# op_amp.net
KiCad netlist of a schematic drawn in Altium Designer
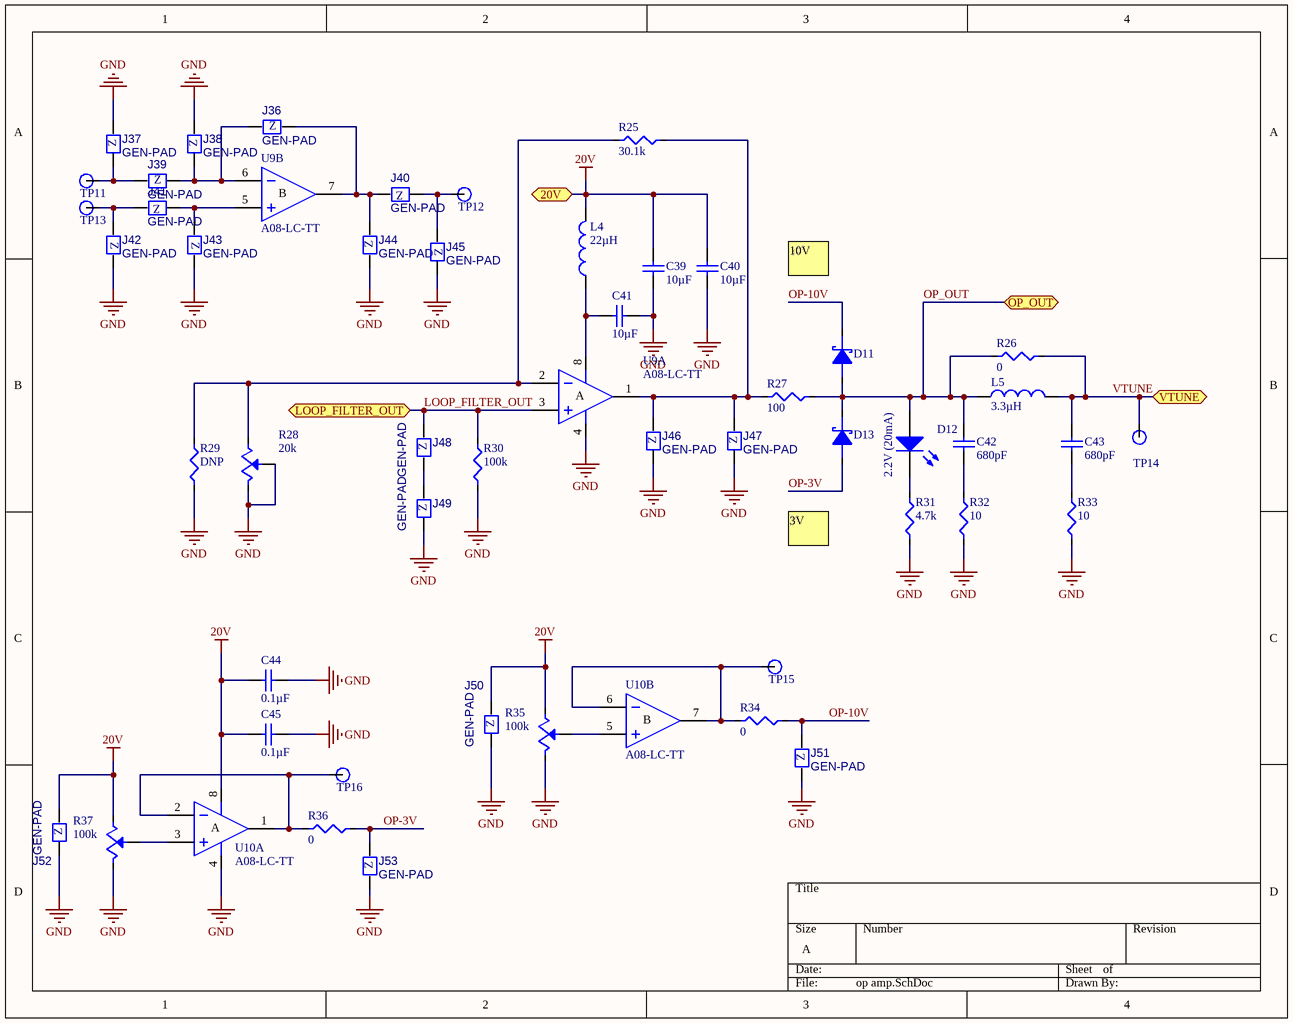
[diagram p0: op amp.SchDoc]

(export (version "E")
  (design (tool "Eeschema 10.0.6"))
  (components
    (comp (ref "C39")
      (value "10µF")
      (footprint "C1210-2.5mm")
      (description "Capacitor")
      (fields (field (name "EE PART NUMBER") "EE-CAP-00013") (field (name "VOLTAGE") "50V"))
      (libsource (lib "EE") (part "CAP"))
    )
    (comp (ref "C40")
      (value "10µF")
      (footprint "C1210-2.5mm")
      (description "Capacitor")
      (fields (field (name "EE PART NUMBER") "EE-CAP-00013") (field (name "VOLTAGE") "50V"))
      (libsource (lib "EE") (part "CAP"))
    )
    (comp (ref "C41")
      (value "10µF")
      (footprint "C1210-2.5mm")
      (description "Capacitor")
      (fields (field (name "EE PART NUMBER") "EE-CAP-00013") (field (name "VOLTAGE") "50V"))
      (libsource (lib "EE") (part "CAP"))
    )
    (comp (ref "C42")
      (value "680pF")
      (footprint "C0805-1.25MM")
      (description "Capacitor")
      (fields (field (name "EE PART NUMBER") "EE-CAP-00012") (field (name "VOLTAGE") "50V"))
      (libsource (lib "EE") (part "CAP"))
    )
    (comp (ref "C43")
      (value "680pF")
      (footprint "C0805-1.25MM")
      (description "Capacitor")
      (fields (field (name "EE PART NUMBER") "EE-CAP-00012") (field (name "VOLTAGE") "50V"))
      (libsource (lib "EE") (part "CAP"))
    )
    (comp (ref "C44")
      (value "0.1µF")
      (footprint "C0805-1.25MM")
      (description "Capacitor")
      (fields (field (name "EE PART NUMBER") "EE-CAP-00014") (field (name "VOLTAGE") "50V"))
      (libsource (lib "EE") (part "CAP"))
    )
    (comp (ref "C45")
      (value "0.1µF")
      (footprint "C0805-1.25MM")
      (description "Capacitor")
      (fields (field (name "EE PART NUMBER") "EE-CAP-00014") (field (name "VOLTAGE") "50V"))
      (libsource (lib "EE") (part "CAP"))
    )
    (comp (ref "D11")
      (value "SCHOTTKY")
      (footprint "SOD-123f")
      (description "Schottky Diode")
      (fields (field (name "EE PART NUMBER") "EE-DIODE-00002") (field (name "VOLTAGE") "30V"))
      (libsource (lib "EE") (part "SCHOTTKY"))
    )
    (comp (ref "D12")
      (value "2.2V (20mA)")
      (footprint "0805-LED")
      (description "LED")
      (fields (field (name "EE PART NUMBER") "EE-DIODE-00003") (field (name "VOLTAGE") "2.2V"))
      (libsource (lib "EE") (part "LED"))
    )
    (comp (ref "D13")
      (value "SCHOTTKY")
      (footprint "SOD-123f")
      (description "Schottky Diode")
      (fields (field (name "EE PART NUMBER") "EE-DIODE-00002") (field (name "VOLTAGE") "30V"))
      (libsource (lib "EE") (part "SCHOTTKY"))
    )
    (comp (ref "J36")
      (value "GEN-PAD")
      (footprint "0805-DNP")
      (description "Generic Component")
      (fields (field (name "EE PART NUMBER") "EE-GEN-00001"))
      (libsource (lib "EE") (part "GEN-PAD"))
    )
    (comp (ref "J37")
      (value "GEN-PAD")
      (footprint "0805-DNP")
      (description "Generic Component")
      (fields (field (name "EE PART NUMBER") "EE-GEN-00001"))
      (libsource (lib "EE") (part "GEN-PAD"))
    )
    (comp (ref "J38")
      (value "GEN-PAD")
      (footprint "0805-DNP")
      (description "Generic Component")
      (fields (field (name "EE PART NUMBER") "EE-GEN-00001"))
      (libsource (lib "EE") (part "GEN-PAD"))
    )
    (comp (ref "J39")
      (value "GEN-PAD")
      (footprint "0805-DNP")
      (description "Generic Component")
      (fields (field (name "EE PART NUMBER") "EE-GEN-00001"))
      (libsource (lib "EE") (part "GEN-PAD"))
    )
    (comp (ref "J40")
      (value "GEN-PAD")
      (footprint "0805-DNP")
      (description "Generic Component")
      (fields (field (name "EE PART NUMBER") "EE-GEN-00001"))
      (libsource (lib "EE") (part "GEN-PAD"))
    )
    (comp (ref "J41")
      (value "GEN-PAD")
      (footprint "0805-DNP")
      (description "Generic Component")
      (fields (field (name "EE PART NUMBER") "EE-GEN-00001"))
      (libsource (lib "EE") (part "GEN-PAD"))
    )
    (comp (ref "J42")
      (value "GEN-PAD")
      (footprint "0805-DNP")
      (description "Generic Component")
      (fields (field (name "EE PART NUMBER") "EE-GEN-00001"))
      (libsource (lib "EE") (part "GEN-PAD"))
    )
    (comp (ref "J43")
      (value "GEN-PAD")
      (footprint "0805-DNP")
      (description "Generic Component")
      (fields (field (name "EE PART NUMBER") "EE-GEN-00001"))
      (libsource (lib "EE") (part "GEN-PAD"))
    )
    (comp (ref "J44")
      (value "GEN-PAD")
      (footprint "0805-DNP")
      (description "Generic Component")
      (fields (field (name "EE PART NUMBER") "EE-GEN-00001"))
      (libsource (lib "EE") (part "GEN-PAD"))
    )
    (comp (ref "J45")
      (value "GEN-PAD")
      (footprint "0805-DNP")
      (description "Generic Component")
      (fields (field (name "EE PART NUMBER") "EE-GEN-00001"))
      (libsource (lib "EE") (part "GEN-PAD"))
    )
    (comp (ref "J46")
      (value "GEN-PAD")
      (footprint "0805-DNP")
      (description "Generic Component")
      (fields (field (name "EE PART NUMBER") "EE-GEN-00001"))
      (libsource (lib "EE") (part "GEN-PAD"))
    )
    (comp (ref "J47")
      (value "GEN-PAD")
      (footprint "0805-DNP")
      (description "Generic Component")
      (fields (field (name "EE PART NUMBER") "EE-GEN-00001"))
      (libsource (lib "EE") (part "GEN-PAD"))
    )
    (comp (ref "J48")
      (value "GEN-PAD")
      (footprint "0805-DNP")
      (description "Generic Component")
      (fields (field (name "EE PART NUMBER") "EE-GEN-00001"))
      (libsource (lib "EE") (part "GEN-PAD"))
    )
    (comp (ref "J49")
      (value "GEN-PAD")
      (footprint "0805-DNP")
      (description "Generic Component")
      (fields (field (name "EE PART NUMBER") "EE-GEN-00001"))
      (libsource (lib "EE") (part "GEN-PAD"))
    )
    (comp (ref "J50")
      (value "GEN-PAD")
      (footprint "0805-DNP")
      (description "Generic Component")
      (fields (field (name "EE PART NUMBER") "EE-GEN-00001"))
      (libsource (lib "EE") (part "GEN-PAD"))
    )
    (comp (ref "J51")
      (value "GEN-PAD")
      (footprint "0805-DNP")
      (description "Generic Component")
      (fields (field (name "EE PART NUMBER") "EE-GEN-00001"))
      (libsource (lib "EE") (part "GEN-PAD"))
    )
    (comp (ref "J52")
      (value "GEN-PAD")
      (footprint "0805-DNP")
      (description "Generic Component")
      (fields (field (name "EE PART NUMBER") "EE-GEN-00001"))
      (libsource (lib "EE") (part "GEN-PAD"))
    )
    (comp (ref "J53")
      (value "GEN-PAD")
      (footprint "0805-DNP")
      (description "Generic Component")
      (fields (field (name "EE PART NUMBER") "EE-GEN-00001"))
      (libsource (lib "EE") (part "GEN-PAD"))
    )
    (comp (ref "L4")
      (value "22µH")
      (footprint "L1210")
      (description "Inductor")
      (fields (field (name "EE PART NUMBER") "EE-L-00005") (field (name "TOLERANCE") "±10%"))
      (libsource (lib "EE") (part "L"))
    )
    (comp (ref "L5")
      (value "3.3µH")
      (footprint "L1210")
      (description "Inductor")
      (fields (field (name "EE PART NUMBER") "EE-L-00006") (field (name "TOLERANCE") "±5%"))
      (libsource (lib "EE") (part "L"))
    )
    (comp (ref "R25")
      (value "30.1k")
      (footprint "0805-0.45MM")
      (fields
        (field (name "EM PART NUMBER") "EM-RES-01089")
        (field (name "TOLERANCE") "1%")
        (field (name "POWER") "0.125W")
      )
      (libsource (lib "EM") (part "RES"))
    )
    (comp (ref "R26")
      (value "0")
      (footprint "0805-0.45MM")
      (fields
        (field (name "EM PART NUMBER") "EM-RES-01617")
        (field (name "POWER") "0.33W")
        (field (name "MANUFACTURER") "Vishay")
      )
      (libsource (lib "EM") (part "RES"))
    )
    (comp (ref "R27")
      (value "100")
      (footprint "0805-0.45MM")
      (fields
        (field (name "EM PART NUMBER") "EM-RES-01370")
        (field (name "TOLERANCE") "1%")
        (field (name "POWER") "0.125W")
      )
      (libsource (lib "EM") (part "RES"))
    )
    (comp (ref "R28")
      (value "20k")
      (footprint "3310Y")
      (description "POTENTIOMETER")
      (fields (field (name "EE PART NUMBER") "EE-POT-00002") (field (name "TOLERANCE") "±20%"))
      (libsource (lib "EE") (part "POT"))
    )
    (comp (ref "R29")
      (value "DNP")
      (footprint "0805-DNP")
      (fields (field (name "EM PART NUMBER") "EM-RES-01607"))
      (libsource (lib "EM") (part "RES"))
    )
    (comp (ref "R30")
      (value "100k")
      (footprint "0805-0.45MM")
      (fields
        (field (name "EM PART NUMBER") "EM-RES-01028")
        (field (name "TOLERANCE") "1%")
        (field (name "POWER") "0.125W")
      )
      (libsource (lib "EM") (part "RES"))
    )
    (comp (ref "R31")
      (value "4.7k")
      (footprint "0805-0.45MM")
      (fields
        (field (name "EM PART NUMBER") "EM-RES-01180")
        (field (name "TOLERANCE") "1%")
        (field (name "POWER") "0.125W")
      )
      (libsource (lib "EM") (part "RES"))
    )
    (comp (ref "R32")
      (value "10")
      (footprint "0805-0.45MM")
      (fields
        (field (name "EM PART NUMBER") "EM-RES-01484")
        (field (name "TOLERANCE") "1%")
        (field (name "POWER") "0.125W")
      )
      (libsource (lib "EM") (part "RES"))
    )
    (comp (ref "R33")
      (value "10")
      (footprint "0805-0.45MM")
      (fields
        (field (name "EM PART NUMBER") "EM-RES-01484")
        (field (name "TOLERANCE") "1%")
        (field (name "POWER") "0.125W")
      )
      (libsource (lib "EM") (part "RES"))
    )
    (comp (ref "R34")
      (value "0")
      (footprint "0805-0.45MM")
      (fields
        (field (name "EM PART NUMBER") "EM-RES-01617")
        (field (name "POWER") "0.33W")
        (field (name "MANUFACTURER") "Vishay")
      )
      (libsource (lib "EM") (part "RES"))
    )
    (comp (ref "R35")
      (value "100k")
      (footprint "3310Y")
      (description "POTENTIOMETER")
      (fields (field (name "EE PART NUMBER") "EE-POT-00003") (field (name "TOLERANCE") "±20%"))
      (libsource (lib "EE") (part "POT"))
    )
    (comp (ref "R36")
      (value "0")
      (footprint "0805-0.45MM")
      (fields
        (field (name "EM PART NUMBER") "EM-RES-01617")
        (field (name "POWER") "0.33W")
        (field (name "MANUFACTURER") "Vishay")
      )
      (libsource (lib "EM") (part "RES"))
    )
    (comp (ref "R37")
      (value "100k")
      (footprint "3310Y")
      (description "POTENTIOMETER")
      (fields (field (name "EE PART NUMBER") "EE-POT-00003") (field (name "TOLERANCE") "±20%"))
      (libsource (lib "EE") (part "POT"))
    )
    (comp (ref "TP11")
      (value "TP-LOOP")
      (footprint "TP-LOOP")
      (fields (field (name "EM PART NUMBER") "EM-TP-00006"))
      (libsource (lib "EM") (part "TP-LOOP"))
    )
    (comp (ref "TP12")
      (value "TP-LOOP")
      (footprint "TP-LOOP")
      (fields (field (name "EM PART NUMBER") "EM-TP-00006"))
      (libsource (lib "EM") (part "TP-LOOP"))
    )
    (comp (ref "TP13")
      (value "TP-LOOP")
      (footprint "TP-LOOP")
      (fields (field (name "EM PART NUMBER") "EM-TP-00006"))
      (libsource (lib "EM") (part "TP-LOOP"))
    )
    (comp (ref "TP14")
      (value "TP-LOOP")
      (footprint "TP-LOOP")
      (fields (field (name "EM PART NUMBER") "EM-TP-00006"))
      (libsource (lib "EM") (part "TP-LOOP"))
    )
    (comp (ref "TP15")
      (value "TP-LOOP")
      (footprint "TP-LOOP")
      (fields (field (name "EM PART NUMBER") "EM-TP-00006"))
      (libsource (lib "EM") (part "TP-LOOP"))
    )
    (comp (ref "TP16")
      (value "TP-LOOP")
      (footprint "TP-LOOP")
      (fields (field (name "EM PART NUMBER") "EM-TP-00006"))
      (libsource (lib "EM") (part "TP-LOOP"))
    )
    (comp (ref "U9")
      (value "A08-LC-TT")
      (footprint "PDIP-8-(7.62mm)-SOCKET")
      (description "OP284")
      (fields (field (name "EE PART NUMBER") "EE-OPAMP-00002") (field (name "MANUFACTURER") "Assmann"))
      (libsource (lib "EE") (part "OP284"))
    )
    (comp (ref "U10")
      (value "A08-LC-TT")
      (footprint "PDIP-8-(7.62mm)-SOCKET")
      (description "OP284")
      (fields (field (name "EE PART NUMBER") "EE-OPAMP-00002") (field (name "MANUFACTURER") "Assmann"))
      (libsource (lib "EE") (part "OP284"))
    )
  )
  (nets
    (net (code "1") (name "/LOOP_FILTER_OUT") (class "Default")
      (node (ref "J48") (pin "1") (pinfunction "1_1") (pintype "passive"))
      (node (ref "R30") (pin "2") (pinfunction "2_2") (pintype "passive"))
      (node (ref "U9") (pin "3") (pinfunction "IN+_3") (pintype "passive"))
    )
    (net (code "2") (name "/OP-3V") (class "Default")
      (node (ref "D13") (pin "A") (pinfunction "A_A") (pintype "passive"))
      (node (ref "J53") (pin "1") (pinfunction "1_1") (pintype "passive"))
      (node (ref "R36") (pin "2") (pinfunction "2_2") (pintype "passive"))
    )
    (net (code "3") (name "/OP-10V") (class "Default")
      (node (ref "D11") (pin "C") (pinfunction "C_C") (pintype "passive"))
      (node (ref "J51") (pin "1") (pinfunction "1_1") (pintype "passive"))
      (node (ref "R34") (pin "2") (pinfunction "2_2") (pintype "passive"))
    )
    (net (code "4") (name "/OP_OUT") (class "Default")
      (node (ref "C42") (pin "2") (pinfunction "2_2") (pintype "passive"))
      (node (ref "D11") (pin "A") (pinfunction "A_A") (pintype "passive"))
      (node (ref "D12") (pin "A") (pinfunction "A_A") (pintype "passive"))
      (node (ref "D13") (pin "C") (pinfunction "C_C") (pintype "passive"))
      (node (ref "L5") (pin "1") (pinfunction "1_1") (pintype "passive"))
      (node (ref "R26") (pin "1") (pinfunction "1_1") (pintype "passive"))
      (node (ref "R27") (pin "2") (pinfunction "2_2") (pintype "passive"))
    )
    (net (code "5") (name "/VTUNE") (class "Default")
      (node (ref "C43") (pin "2") (pinfunction "2_2") (pintype "passive"))
      (node (ref "L5") (pin "2") (pinfunction "2_2") (pintype "passive"))
      (node (ref "R26") (pin "2") (pinfunction "2_2") (pintype "passive"))
      (node (ref "TP14") (pin "0") (pinfunction "0_0") (pintype "passive"))
    )
    (net (code "6") (name "20V") (class "Default")
      (node (ref "C39") (pin "2") (pinfunction "2_2") (pintype "passive"))
      (node (ref "C40") (pin "2") (pinfunction "2_2") (pintype "passive"))
      (node (ref "C44") (pin "1") (pinfunction "1_1") (pintype "passive"))
      (node (ref "C45") (pin "1") (pinfunction "1_1") (pintype "passive"))
      (node (ref "J50") (pin "1") (pinfunction "1_1") (pintype "passive"))
      (node (ref "J52") (pin "1") (pinfunction "1_1") (pintype "passive"))
      (node (ref "L4") (pin "2") (pinfunction "2_2") (pintype "passive"))
      (node (ref "R35") (pin "1") (pinfunction "1_1") (pintype "passive"))
      (node (ref "R37") (pin "1") (pinfunction "1_1") (pintype "passive"))
      (node (ref "U10") (pin "8") (pinfunction "V+_8") (pintype "power_in"))
    )
    (net (code "7") (name "GND") (class "Default")
      (node (ref "C39") (pin "1") (pinfunction "1_1") (pintype "passive"))
      (node (ref "C40") (pin "1") (pinfunction "1_1") (pintype "passive"))
      (node (ref "C41") (pin "2") (pinfunction "2_2") (pintype "passive"))
      (node (ref "C44") (pin "2") (pinfunction "2_2") (pintype "passive"))
      (node (ref "C45") (pin "2") (pinfunction "2_2") (pintype "passive"))
      (node (ref "J37") (pin "1") (pinfunction "1_1") (pintype "passive"))
      (node (ref "J38") (pin "1") (pinfunction "1_1") (pintype "passive"))
      (node (ref "J42") (pin "1") (pinfunction "1_1") (pintype "passive"))
      (node (ref "J43") (pin "1") (pinfunction "1_1") (pintype "passive"))
      (node (ref "J44") (pin "2") (pinfunction "2_2") (pintype "passive"))
      (node (ref "J45") (pin "1") (pinfunction "1_1") (pintype "passive"))
      (node (ref "J46") (pin "2") (pinfunction "2_2") (pintype "passive"))
      (node (ref "J47") (pin "2") (pinfunction "2_2") (pintype "passive"))
      (node (ref "J49") (pin "2") (pinfunction "2_2") (pintype "passive"))
      (node (ref "J50") (pin "2") (pinfunction "2_2") (pintype "passive"))
      (node (ref "J51") (pin "2") (pinfunction "2_2") (pintype "passive"))
      (node (ref "J52") (pin "2") (pinfunction "2_2") (pintype "passive"))
      (node (ref "J53") (pin "2") (pinfunction "2_2") (pintype "passive"))
      (node (ref "R28") (pin "2") (pinfunction "2_2") (pintype "passive"))
      (node (ref "R28") (pin "3") (pinfunction "3_3") (pintype "passive"))
      (node (ref "R29") (pin "1") (pinfunction "1_1") (pintype "passive"))
      (node (ref "R30") (pin "1") (pinfunction "1_1") (pintype "passive"))
      (node (ref "R31") (pin "1") (pinfunction "1_1") (pintype "passive"))
      (node (ref "R32") (pin "1") (pinfunction "1_1") (pintype "passive"))
      (node (ref "R33") (pin "1") (pinfunction "1_1") (pintype "passive"))
      (node (ref "R35") (pin "3") (pinfunction "3_3") (pintype "passive"))
      (node (ref "R37") (pin "3") (pinfunction "3_3") (pintype "passive"))
      (node (ref "U10") (pin "4") (pinfunction "V-_4") (pintype "power_in"))
      (node (ref "U9") (pin "4") (pinfunction "V-_4") (pintype "power_in"))
    )
    (net (code "8") (name "Net-(C42-Pad1)") (class "Default")
      (node (ref "C42") (pin "1") (pinfunction "1_1") (pintype "passive"))
      (node (ref "R32") (pin "2") (pinfunction "2_2") (pintype "passive"))
    )
    (net (code "9") (name "Net-(C43-Pad1)") (class "Default")
      (node (ref "C43") (pin "1") (pinfunction "1_1") (pintype "passive"))
      (node (ref "R33") (pin "2") (pinfunction "2_2") (pintype "passive"))
    )
    (net (code "10") (name "Net-(D12-PadC)") (class "Default")
      (node (ref "D12") (pin "C") (pinfunction "C_C") (pintype "passive"))
      (node (ref "R31") (pin "2") (pinfunction "2_2") (pintype "passive"))
    )
    (net (code "11") (name "Net-(J37-Pad2)") (class "Default")
      (node (ref "J37") (pin "2") (pinfunction "2_2") (pintype "passive"))
      (node (ref "J39") (pin "2") (pinfunction "2_2") (pintype "passive"))
      (node (ref "TP11") (pin "0") (pinfunction "0_0") (pintype "passive"))
    )
    (net (code "12") (name "Net-(J40-Pad2)") (class "Default")
      (node (ref "J40") (pin "2") (pinfunction "2_2") (pintype "passive"))
      (node (ref "J45") (pin "2") (pinfunction "2_2") (pintype "passive"))
      (node (ref "TP12") (pin "0") (pinfunction "0_0") (pintype "passive"))
    )
    (net (code "13") (name "Net-(J41-Pad1)") (class "Default")
      (node (ref "J41") (pin "1") (pinfunction "1_1") (pintype "passive"))
      (node (ref "J42") (pin "2") (pinfunction "2_2") (pintype "passive"))
      (node (ref "TP13") (pin "0") (pinfunction "0_0") (pintype "passive"))
    )
    (net (code "14") (name "Net-(J48-Pad2)") (class "Default")
      (node (ref "J48") (pin "2") (pinfunction "2_2") (pintype "passive"))
      (node (ref "J49") (pin "1") (pinfunction "1_1") (pintype "passive"))
    )
    (net (code "15") (name "Net-(U9A-IN-)") (class "Default")
      (node (ref "R25") (pin "1") (pinfunction "1_1") (pintype "passive"))
      (node (ref "R28") (pin "1") (pinfunction "1_1") (pintype "passive"))
      (node (ref "R29") (pin "2") (pinfunction "2_2") (pintype "passive"))
      (node (ref "U9") (pin "2") (pinfunction "IN-_2") (pintype "passive"))
    )
    (net (code "16") (name "Net-(U9A-OUT)") (class "Default")
      (node (ref "J46") (pin "1") (pinfunction "1_1") (pintype "passive"))
      (node (ref "J47") (pin "1") (pinfunction "1_1") (pintype "passive"))
      (node (ref "R25") (pin "2") (pinfunction "2_2") (pintype "passive"))
      (node (ref "R27") (pin "1") (pinfunction "1_1") (pintype "passive"))
      (node (ref "U9") (pin "1") (pinfunction "OUT_1") (pintype "passive"))
    )
    (net (code "17") (name "Net-(U9A-V+)") (class "Default")
      (node (ref "C41") (pin "1") (pinfunction "1_1") (pintype "passive"))
      (node (ref "L4") (pin "1") (pinfunction "1_1") (pintype "passive"))
      (node (ref "U9") (pin "8") (pinfunction "V+_8") (pintype "power_in"))
    )
    (net (code "18") (name "Net-(U9B-6)") (class "Default")
      (node (ref "J36") (pin "1") (pinfunction "1_1") (pintype "passive"))
      (node (ref "J40") (pin "1") (pinfunction "1_1") (pintype "passive"))
      (node (ref "J44") (pin "1") (pinfunction "1_1") (pintype "passive"))
      (node (ref "U9") (pin "7") (pinfunction "6_7") (pintype "passive"))
    )
    (net (code "19") (name "Net-(U9B-IN+)") (class "Default")
      (node (ref "J41") (pin "2") (pinfunction "2_2") (pintype "passive"))
      (node (ref "J43") (pin "2") (pinfunction "2_2") (pintype "passive"))
      (node (ref "U9") (pin "5") (pinfunction "IN+_5") (pintype "passive"))
    )
    (net (code "20") (name "Net-(U9B-IN-)") (class "Default")
      (node (ref "J36") (pin "2") (pinfunction "2_2") (pintype "passive"))
      (node (ref "J38") (pin "2") (pinfunction "2_2") (pintype "passive"))
      (node (ref "J39") (pin "1") (pinfunction "1_1") (pintype "passive"))
      (node (ref "U9") (pin "6") (pinfunction "IN-_6") (pintype "passive"))
    )
    (net (code "21") (name "Net-(U10A-IN+)") (class "Default")
      (node (ref "R37") (pin "2") (pinfunction "2_2") (pintype "passive"))
      (node (ref "U10") (pin "3") (pinfunction "IN+_3") (pintype "passive"))
    )
    (net (code "22") (name "Net-(U10A-IN-)") (class "Default")
      (node (ref "R36") (pin "1") (pinfunction "1_1") (pintype "passive"))
      (node (ref "TP16") (pin "0") (pinfunction "0_0") (pintype "passive"))
      (node (ref "U10") (pin "1") (pinfunction "OUT_1") (pintype "passive"))
      (node (ref "U10") (pin "2") (pinfunction "IN-_2") (pintype "passive"))
    )
    (net (code "23") (name "Net-(U10B-6)") (class "Default")
      (node (ref "R34") (pin "1") (pinfunction "1_1") (pintype "passive"))
      (node (ref "TP15") (pin "0") (pinfunction "0_0") (pintype "passive"))
      (node (ref "U10") (pin "6") (pinfunction "IN-_6") (pintype "passive"))
      (node (ref "U10") (pin "7") (pinfunction "6_7") (pintype "passive"))
    )
    (net (code "24") (name "Net-(U10B-IN+)") (class "Default")
      (node (ref "R35") (pin "2") (pinfunction "2_2") (pintype "passive"))
      (node (ref "U10") (pin "5") (pinfunction "IN+_5") (pintype "passive"))
    )
  )
)
